# cpx-synth1-panel.net
KiCad netlist of a schematic drawn in EAGLE
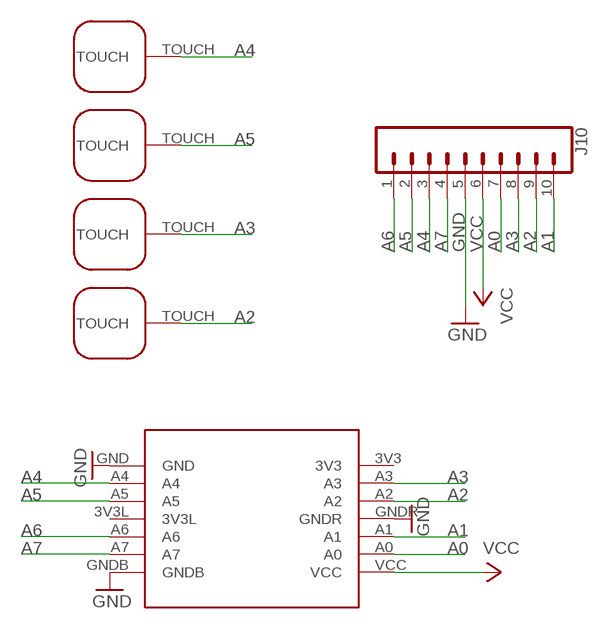
[diagram p0: schematic, sheet 1]

(export (version "E")
  (design (tool "Eeschema 10.0.6"))
  (components
    (comp (ref "J10")
      (value "CONN_10\"")
      (footprint "eagle-import:1X10")
      (libsource (lib "eagle-import") (part "CONN_10{dblquote}"))
    )
    (comp (ref "T1")
      (value "TOUCHPADROUND1")
      (footprint "eagle-import:TOUCHPAD1")
      (libsource (lib "eagle-import") (part "TOUCHPADROUND1"))
    )
    (comp (ref "T2")
      (value "TOUCHPADROUND1")
      (footprint "eagle-import:TOUCHPAD1")
      (libsource (lib "eagle-import") (part "TOUCHPADROUND1"))
    )
    (comp (ref "T3")
      (value "TOUCHPADROUND1")
      (footprint "eagle-import:TOUCHPAD1")
      (libsource (lib "eagle-import") (part "TOUCHPADROUND1"))
    )
    (comp (ref "T4")
      (value "TOUCHPADROUND1")
      (footprint "eagle-import:TOUCHPAD1")
      (libsource (lib "eagle-import") (part "TOUCHPADROUND1"))
    )
    (comp (ref "U1")
      (value "CIRCUITPLAYGROUNDEXPRESS")
      (footprint "eagle-import:CIRCUITPLAYGROUNDEXPRESS")
      (libsource (lib "eagle-import") (part "CIRCUITPLAYGROUNDEXPRESS"))
    )
  )
  (nets
    (net (code "1") (name "/A0") (class "Default")
      (node (ref "J10") (pin "7") (pinfunction "7_7") (pintype "passive"))
      (node (ref "U1") (pin "A0") (pinfunction "A0_A0") (pintype "bidirectional"))
    )
    (net (code "2") (name "/A1") (class "Default")
      (node (ref "J10") (pin "10") (pinfunction "10_10") (pintype "passive"))
      (node (ref "U1") (pin "A1") (pinfunction "A1_A1") (pintype "bidirectional"))
    )
    (net (code "3") (name "/A2") (class "Default")
      (node (ref "J10") (pin "9") (pinfunction "9_9") (pintype "passive"))
      (node (ref "T4") (pin "TOUCH") (pinfunction "TOUCH_TOUCH") (pintype "bidirectional"))
      (node (ref "U1") (pin "A2") (pinfunction "A2_A2") (pintype "bidirectional"))
    )
    (net (code "4") (name "/A3") (class "Default")
      (node (ref "J10") (pin "8") (pinfunction "8_8") (pintype "passive"))
      (node (ref "T1") (pin "TOUCH") (pinfunction "TOUCH_TOUCH") (pintype "bidirectional"))
      (node (ref "U1") (pin "A3") (pinfunction "A3_A3") (pintype "bidirectional"))
    )
    (net (code "5") (name "/A4") (class "Default")
      (node (ref "J10") (pin "3") (pinfunction "3_3") (pintype "passive"))
      (node (ref "T3") (pin "TOUCH") (pinfunction "TOUCH_TOUCH") (pintype "bidirectional"))
      (node (ref "U1") (pin "A4") (pinfunction "A4_A4") (pintype "bidirectional"))
    )
    (net (code "6") (name "/A5") (class "Default")
      (node (ref "J10") (pin "2") (pinfunction "2_2") (pintype "passive"))
      (node (ref "T2") (pin "TOUCH") (pinfunction "TOUCH_TOUCH") (pintype "bidirectional"))
      (node (ref "U1") (pin "A5") (pinfunction "A5_A5") (pintype "bidirectional"))
    )
    (net (code "7") (name "/A6") (class "Default")
      (node (ref "J10") (pin "1") (pinfunction "1_1") (pintype "passive"))
      (node (ref "U1") (pin "A6") (pinfunction "A6_A6") (pintype "bidirectional"))
    )
    (net (code "8") (name "/A7") (class "Default")
      (node (ref "J10") (pin "4") (pinfunction "4_4") (pintype "passive"))
      (node (ref "U1") (pin "A7") (pinfunction "A7_A7") (pintype "bidirectional"))
    )
    (net (code "9") (name "GND") (class "Default")
      (node (ref "J10") (pin "5") (pinfunction "5_5") (pintype "passive"))
      (node (ref "U1") (pin "GND") (pinfunction "GND_GND") (pintype "bidirectional"))
      (node (ref "U1") (pin "GNDB") (pinfunction "GNDB_GNDB") (pintype "bidirectional"))
      (node (ref "U1") (pin "GNDR") (pinfunction "GNDR_GNDR") (pintype "bidirectional"))
    )
    (net (code "10") (name "VCC") (class "Default")
      (node (ref "J10") (pin "6") (pinfunction "6_6") (pintype "passive"))
      (node (ref "U1") (pin "VCC") (pinfunction "VCC_VCC") (pintype "bidirectional"))
    )
    (net (code "11") (name "unconnected-(U1-Pad3V3)") (class "Default")
      (node (ref "U1") (pin "3V3") (pinfunction "3V3_3V3") (pintype "bidirectional"))
    )
    (net (code "12") (name "unconnected-(U1-Pad3V3L)") (class "Default")
      (node (ref "U1") (pin "3V3L") (pinfunction "3V3L_3V3L") (pintype "bidirectional"))
    )
  )
)
